# Finger_Password_Keyboard.net
KiCad netlist of a schematic drawn in EAGLE
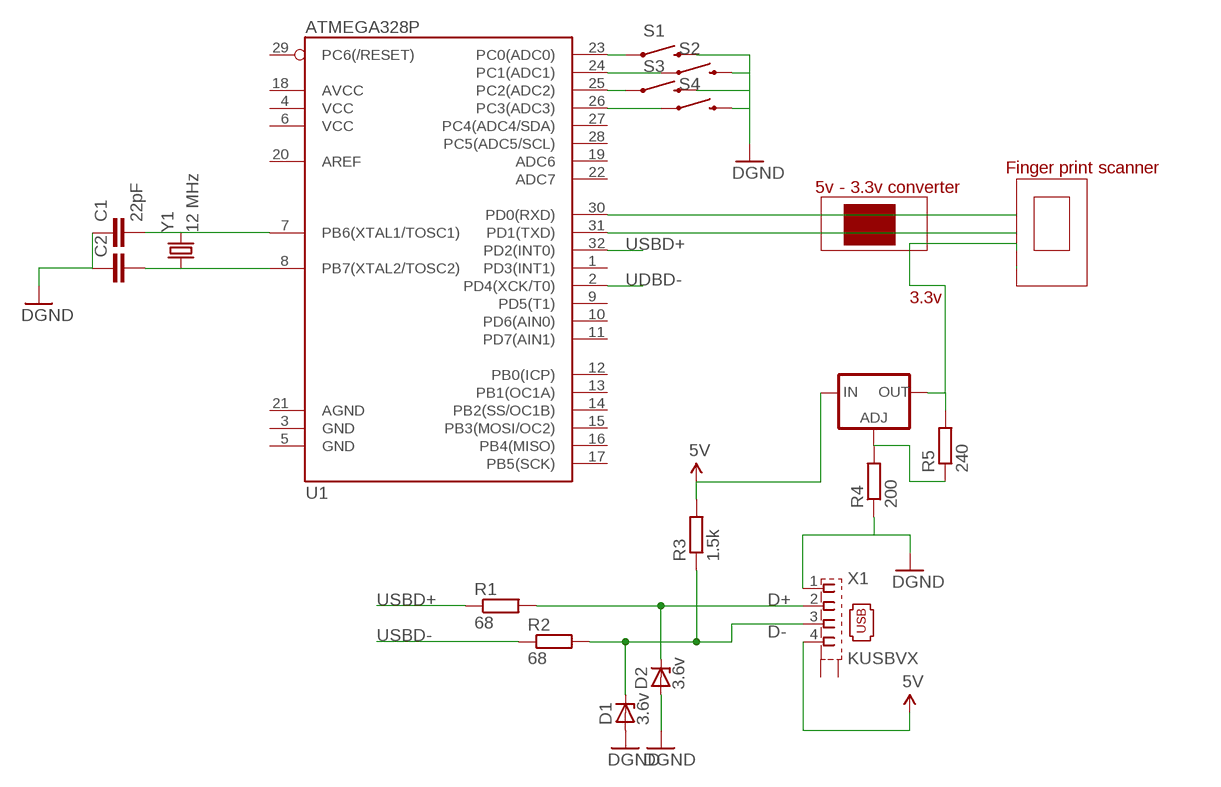
[diagram p0: schematic, sheet 1]

(export (version "E")
  (design (tool "Eeschema 10.0.6"))
  (components
    (comp (ref "C1")
      (value "22pF")
      (footprint "eagle-import:0402-CAP")
      (libsource (lib "eagle-import") (part "CAP0402-CAP"))
    )
    (comp (ref "C2")
      (value "CAP0402-CAP")
      (footprint "eagle-import:0402-CAP")
      (libsource (lib "eagle-import") (part "CAP0402-CAP"))
    )
    (comp (ref "D1")
      (value "3.6v")
      (footprint "eagle-import:C1702-15")
      (libsource (lib "eagle-import") (part "ZENER-DIODEC1702-15"))
    )
    (comp (ref "D2")
      (value "3.6v")
      (footprint "eagle-import:C1702-15")
      (libsource (lib "eagle-import") (part "ZENER-DIODEC1702-15"))
    )
    (comp (ref "R1")
      (value "68")
      (footprint "eagle-import:0204_7")
      (libsource (lib "eagle-import") (part "R-EU_0204/7"))
    )
    (comp (ref "R2")
      (value "68")
      (footprint "eagle-import:0204_7")
      (libsource (lib "eagle-import") (part "R-EU_0204/7"))
    )
    (comp (ref "R3")
      (value "1.5k")
      (footprint "eagle-import:0204_7")
      (libsource (lib "eagle-import") (part "R-EU_0204/7"))
    )
    (comp (ref "R4")
      (value "200")
      (footprint "eagle-import:0204V")
      (libsource (lib "eagle-import") (part "R-EU_0204/2V"))
    )
    (comp (ref "R5")
      (value "240")
      (footprint "eagle-import:0204V")
      (libsource (lib "eagle-import") (part "R-EU_0204/2V"))
    )
    (comp (ref "S1")
      (value "SWITCH-MOMENTARY-2PTH")
      (footprint "eagle-import:TACTILE-PTH")
      (libsource (lib "eagle-import") (part "SWITCH-MOMENTARY-2PTH"))
    )
    (comp (ref "S2")
      (value "SWITCH-MOMENTARY-2PTH")
      (footprint "eagle-import:TACTILE-PTH")
      (libsource (lib "eagle-import") (part "SWITCH-MOMENTARY-2PTH"))
    )
    (comp (ref "S3")
      (value "SWITCH-MOMENTARY-2PTH")
      (footprint "eagle-import:TACTILE-PTH")
      (libsource (lib "eagle-import") (part "SWITCH-MOMENTARY-2PTH"))
    )
    (comp (ref "S4")
      (value "SWITCH-MOMENTARY-2PTH")
      (footprint "eagle-import:TACTILE-PTH")
      (libsource (lib "eagle-import") (part "SWITCH-MOMENTARY-2PTH"))
    )
    (comp (ref "U1")
      (value "ATMEGA328P")
      (footprint "eagle-import:TQFP32-08")
      (libsource (lib "eagle-import") (part "ATMEGA328_SMT"))
    )
    (comp (ref "U2")
      (value "V_REG_317SINK")
      (footprint "eagle-import:TO220-ADJ")
      (libsource (lib "eagle-import") (part "V_REG_317SINK"))
    )
    (comp (ref "X1")
      (value "KUSBVX")
      (footprint "eagle-import:KUSBVX")
      (libsource (lib "eagle-import") (part "KUSBVX"))
    )
    (comp (ref "Y1")
      (value "12 MHz")
      (footprint "eagle-import:HC49U-V")
      (libsource (lib "eagle-import") (part "CRYSTALHC49UV"))
    )
  )
  (nets
    (net (code "1") (name "/UDBD-") (class "Default")
      (node (ref "U1") (pin "2") (pinfunction "PD4(XCK/T0)_2") (pintype "bidirectional"))
    )
    (net (code "2") (name "/USBD+") (class "Default")
      (node (ref "R1") (pin "1") (pinfunction "1_1") (pintype "passive"))
      (node (ref "U1") (pin "32") (pinfunction "PD2(INT0)_32") (pintype "bidirectional"))
    )
    (net (code "3") (name "/USBD-") (class "Default")
      (node (ref "R2") (pin "1") (pinfunction "1_1") (pintype "passive"))
    )
    (net (code "4") (name "5V") (class "Default")
      (node (ref "R3") (pin "2") (pinfunction "2_2") (pintype "passive"))
      (node (ref "U2") (pin "IN") (pinfunction "IN_IN") (pintype "input"))
      (node (ref "X1") (pin "4") (pinfunction "4_4") (pintype "passive"))
    )
    (net (code "5") (name "DGND") (class "Default")
      (node (ref "C1") (pin "1") (pinfunction "1_1") (pintype "passive"))
      (node (ref "C2") (pin "1") (pinfunction "1_1") (pintype "passive"))
      (node (ref "D1") (pin "A") (pinfunction "A_A") (pintype "passive"))
      (node (ref "D2") (pin "A") (pinfunction "A_A") (pintype "passive"))
      (node (ref "R4") (pin "1") (pinfunction "1_1") (pintype "passive"))
      (node (ref "S1") (pin "3") (pinfunction "2_3") (pintype "passive"))
      (node (ref "S2") (pin "3") (pinfunction "2_3") (pintype "passive"))
      (node (ref "S3") (pin "3") (pinfunction "2_3") (pintype "passive"))
      (node (ref "S4") (pin "3") (pinfunction "2_3") (pintype "passive"))
      (node (ref "X1") (pin "1") (pinfunction "1_1") (pintype "passive"))
    )
    (net (code "6") (name "Net-(D1-PadC)") (class "Default")
      (node (ref "D1") (pin "C") (pinfunction "C_C") (pintype "passive"))
      (node (ref "R2") (pin "2") (pinfunction "2_2") (pintype "passive"))
      (node (ref "R3") (pin "1") (pinfunction "1_1") (pintype "passive"))
      (node (ref "X1") (pin "3") (pinfunction "3_3") (pintype "passive"))
    )
    (net (code "7") (name "Net-(D2-PadC)") (class "Default")
      (node (ref "D2") (pin "C") (pinfunction "C_C") (pintype "passive"))
      (node (ref "R1") (pin "2") (pinfunction "2_2") (pintype "passive"))
      (node (ref "X1") (pin "2") (pinfunction "2_2") (pintype "passive"))
    )
    (net (code "8") (name "Net-(R4-Pad2)") (class "Default")
      (node (ref "R4") (pin "2") (pinfunction "2_2") (pintype "passive"))
      (node (ref "R5") (pin "1") (pinfunction "1_1") (pintype "passive"))
      (node (ref "U2") (pin "ADJ") (pinfunction "ADJ_ADJ") (pintype "input"))
    )
    (net (code "9") (name "Net-(R5-Pad2)") (class "Default")
      (node (ref "R5") (pin "2") (pinfunction "2_2") (pintype "passive"))
      (node (ref "U2") (pin "OUT") (pinfunction "OUT_OUT") (pintype "output"))
    )
    (net (code "10") (name "Net-(U1-PB6(XTAL1{slash}TOSC1))") (class "Default")
      (node (ref "C1") (pin "2") (pinfunction "2_2") (pintype "passive"))
      (node (ref "U1") (pin "7") (pinfunction "PB6(XTAL1/TOSC1)_7") (pintype "bidirectional"))
      (node (ref "Y1") (pin "2") (pinfunction "2_2") (pintype "passive"))
    )
    (net (code "11") (name "Net-(U1-PB7(XTAL2{slash}TOSC2))") (class "Default")
      (node (ref "C2") (pin "2") (pinfunction "2_2") (pintype "passive"))
      (node (ref "U1") (pin "8") (pinfunction "PB7(XTAL2/TOSC2)_8") (pintype "bidirectional"))
      (node (ref "Y1") (pin "1") (pinfunction "1_1") (pintype "passive"))
    )
    (net (code "12") (name "Net-(U1-PC0(ADC0))") (class "Default")
      (node (ref "S1") (pin "1") (pinfunction "1_1") (pintype "passive"))
      (node (ref "U1") (pin "23") (pinfunction "PC0(ADC0)_23") (pintype "bidirectional"))
    )
    (net (code "13") (name "Net-(U1-PC1(ADC1))") (class "Default")
      (node (ref "S2") (pin "1") (pinfunction "1_1") (pintype "passive"))
      (node (ref "U1") (pin "24") (pinfunction "PC1(ADC1)_24") (pintype "bidirectional"))
    )
    (net (code "14") (name "Net-(U1-PC2(ADC2))") (class "Default")
      (node (ref "S3") (pin "1") (pinfunction "1_1") (pintype "passive"))
      (node (ref "U1") (pin "25") (pinfunction "PC2(ADC2)_25") (pintype "bidirectional"))
    )
    (net (code "15") (name "Net-(U1-PC3(ADC3))") (class "Default")
      (node (ref "S4") (pin "1") (pinfunction "1_1") (pintype "passive"))
      (node (ref "U1") (pin "26") (pinfunction "PC3(ADC3)_26") (pintype "bidirectional"))
    )
    (net (code "16") (name "unconnected-(U1-ADC6-Pad19)") (class "Default")
      (node (ref "U1") (pin "19") (pinfunction "ADC6_19") (pintype "bidirectional"))
    )
    (net (code "17") (name "unconnected-(U1-ADC7-Pad22)") (class "Default")
      (node (ref "U1") (pin "22") (pinfunction "ADC7_22") (pintype "bidirectional"))
    )
    (net (code "18") (name "unconnected-(U1-AGND-Pad21)") (class "Default")
      (node (ref "U1") (pin "21") (pinfunction "AGND_21") (pintype "bidirectional"))
    )
    (net (code "19") (name "unconnected-(U1-AREF-Pad20)") (class "Default")
      (node (ref "U1") (pin "20") (pinfunction "AREF_20") (pintype "bidirectional"))
    )
    (net (code "20") (name "unconnected-(U1-AVCC-Pad18)") (class "Default")
      (node (ref "U1") (pin "18") (pinfunction "AVCC_18") (pintype "bidirectional"))
    )
    (net (code "21") (name "unconnected-(U1-GND-Pad3)") (class "Default")
      (node (ref "U1") (pin "3") (pinfunction "GND_3") (pintype "bidirectional"))
    )
    (net (code "22") (name "unconnected-(U1-GND-Pad5)") (class "Default")
      (node (ref "U1") (pin "5") (pinfunction "GND_5") (pintype "bidirectional"))
    )
    (net (code "23") (name "unconnected-(U1-PB0(ICP)-Pad12)") (class "Default")
      (node (ref "U1") (pin "12") (pinfunction "PB0(ICP)_12") (pintype "bidirectional"))
    )
    (net (code "24") (name "unconnected-(U1-PB1(OC1A)-Pad13)") (class "Default")
      (node (ref "U1") (pin "13") (pinfunction "PB1(OC1A)_13") (pintype "bidirectional"))
    )
    (net (code "25") (name "unconnected-(U1-PB2(SS{slash}OC1B)-Pad14)") (class "Default")
      (node (ref "U1") (pin "14") (pinfunction "PB2(SS/OC1B)_14") (pintype "bidirectional"))
    )
    (net (code "26") (name "unconnected-(U1-PB3(MOSI{slash}OC2)-Pad15)") (class "Default")
      (node (ref "U1") (pin "15") (pinfunction "PB3(MOSI/OC2)_15") (pintype "bidirectional"))
    )
    (net (code "27") (name "unconnected-(U1-PB4(MISO)-Pad16)") (class "Default")
      (node (ref "U1") (pin "16") (pinfunction "PB4(MISO)_16") (pintype "bidirectional"))
    )
    (net (code "28") (name "unconnected-(U1-PB5(SCK)-Pad17)") (class "Default")
      (node (ref "U1") (pin "17") (pinfunction "PB5(SCK)_17") (pintype "bidirectional"))
    )
    (net (code "29") (name "unconnected-(U1-PC4(ADC4{slash}SDA)-Pad27)") (class "Default")
      (node (ref "U1") (pin "27") (pinfunction "PC4(ADC4/SDA)_27") (pintype "bidirectional"))
    )
    (net (code "30") (name "unconnected-(U1-PC5(ADC5{slash}SCL)-Pad28)") (class "Default")
      (node (ref "U1") (pin "28") (pinfunction "PC5(ADC5/SCL)_28") (pintype "bidirectional"))
    )
    (net (code "31") (name "unconnected-(U1-PC6({slash}RESET)-Pad29)") (class "Default")
      (node (ref "U1") (pin "29") (pinfunction "PC6(/RESET)_29") (pintype "bidirectional"))
    )
    (net (code "32") (name "unconnected-(U1-PD0(RXD)-Pad30)") (class "Default")
      (node (ref "U1") (pin "30") (pinfunction "PD0(RXD)_30") (pintype "bidirectional"))
    )
    (net (code "33") (name "unconnected-(U1-PD1(TXD)-Pad31)") (class "Default")
      (node (ref "U1") (pin "31") (pinfunction "PD1(TXD)_31") (pintype "bidirectional"))
    )
    (net (code "34") (name "unconnected-(U1-PD3(INT1)-Pad1)") (class "Default")
      (node (ref "U1") (pin "1") (pinfunction "PD3(INT1)_1") (pintype "bidirectional"))
    )
    (net (code "35") (name "unconnected-(U1-PD5(T1)-Pad9)") (class "Default")
      (node (ref "U1") (pin "9") (pinfunction "PD5(T1)_9") (pintype "bidirectional"))
    )
    (net (code "36") (name "unconnected-(U1-PD6(AIN0)-Pad10)") (class "Default")
      (node (ref "U1") (pin "10") (pinfunction "PD6(AIN0)_10") (pintype "bidirectional"))
    )
    (net (code "37") (name "unconnected-(U1-PD7(AIN1)-Pad11)") (class "Default")
      (node (ref "U1") (pin "11") (pinfunction "PD7(AIN1)_11") (pintype "bidirectional"))
    )
    (net (code "38") (name "unconnected-(U1-VCC-Pad4)") (class "Default")
      (node (ref "U1") (pin "4") (pinfunction "VCC_4") (pintype "bidirectional"))
    )
    (net (code "39") (name "unconnected-(U1-VCC-Pad6)") (class "Default")
      (node (ref "U1") (pin "6") (pinfunction "VCC_6") (pintype "bidirectional"))
    )
    (net (code "40") (name "unconnected-(X1-S1-PadM1)") (class "Default")
      (node (ref "X1") (pin "M1") (pinfunction "S1_M1") (pintype "passive"))
    )
    (net (code "41") (name "unconnected-(X1-S2-PadM2)") (class "Default")
      (node (ref "X1") (pin "M2") (pinfunction "S2_M2") (pintype "passive"))
    )
  )
)
